# PCB.net
KiCad netlist of a schematic drawn in Altium Designer
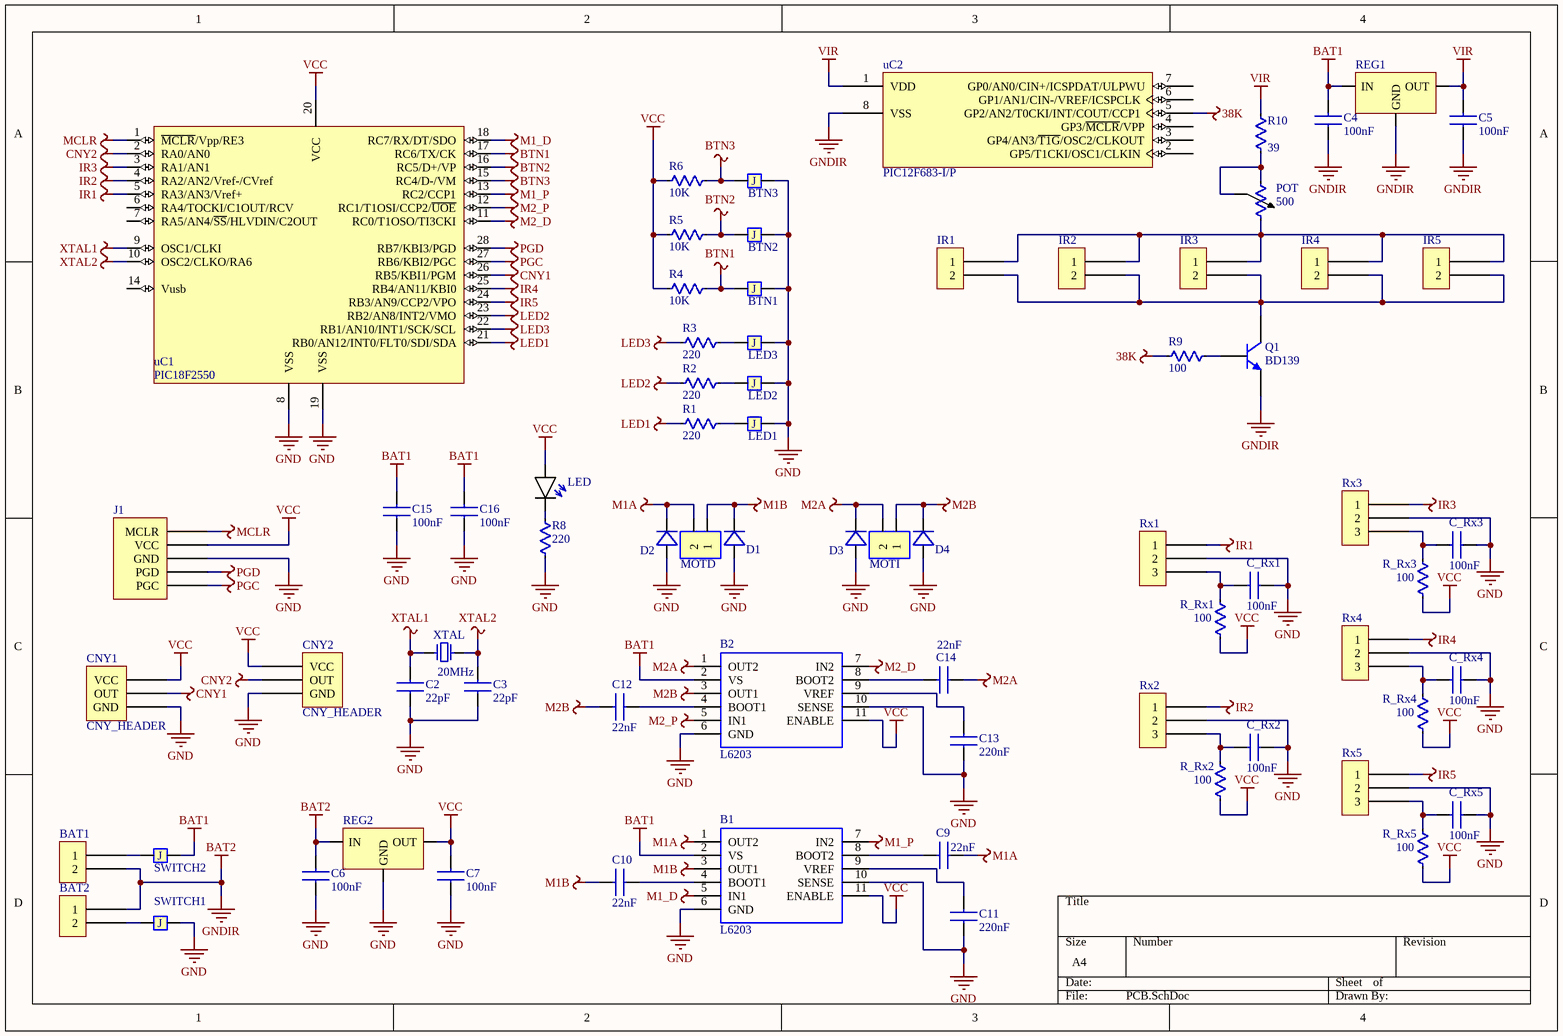
[diagram p0: PCB.SchDoc]

(export (version "E")
  (design (tool "Eeschema 10.0.6"))
  (components
    (comp (ref "B1") (value "L6203") (footprint "MUTIWATT11") (libsource (lib "L6203") (part "L6203")))
    (comp (ref "B2") (value "L6203") (footprint "MUTIWATT11") (libsource (lib "L6203") (part "L6203")))
    (comp (ref "BAT1")
      (value "~")
      (footprint "HEADER 1x2")
      (libsource (lib "AltiumLibrary") (part "Header 1x2"))
    )
    (comp (ref "BAT2")
      (value "~")
      (footprint "HEADER 1x2")
      (libsource (lib "AltiumLibrary") (part "Header 1x2"))
    )
    (comp (ref "BTN1")
      (value "JUMPER")
      (footprint "JUMPER")
      (libsource (lib "AltiumLibrary") (part "JUMPER"))
    )
    (comp (ref "BTN2")
      (value "JUMPER")
      (footprint "JUMPER")
      (libsource (lib "AltiumLibrary") (part "JUMPER"))
    )
    (comp (ref "BTN3") (value "JUMPER") (footprint "JUMPER") (libsource (lib "") (part "JUMPER_1")))
    (comp (ref "C2")
      (value "22pF")
      (footprint "CAP-CER")
      (fields (field (name "Comment") "CAP-CER"))
      (libsource (lib "AltiumLibrary") (part "CAP-CER"))
    )
    (comp (ref "C3")
      (value "22pF")
      (footprint "CAP-CER")
      (fields (field (name "Comment") "CAP-CER"))
      (libsource (lib "AltiumLibrary") (part "CAP-CER"))
    )
    (comp (ref "C4")
      (value "100nF")
      (footprint "CAP-CER")
      (fields (field (name "Comment") "CAP-CER"))
      (libsource (lib "") (part "CAP-CER_1"))
    )
    (comp (ref "C5")
      (value "100nF")
      (footprint "CAP-CER")
      (fields (field (name "Comment") "CAP-CER"))
      (libsource (lib "") (part "CAP-CER_1"))
    )
    (comp (ref "C6")
      (value "100nF")
      (footprint "CAP-CER")
      (fields (field (name "Comment") "CAP-CER"))
      (libsource (lib "") (part "CAP-CER_1"))
    )
    (comp (ref "C7")
      (value "100nF")
      (footprint "CAP-CER")
      (fields (field (name "Comment") "CAP-CER"))
      (libsource (lib "") (part "CAP-CER_1"))
    )
    (comp (ref "C9")
      (value "22nF")
      (footprint "CAP-CER")
      (fields (field (name "Comment") "CAP-CER"))
      (libsource (lib "") (part "CAP-CER_1"))
    )
    (comp (ref "C10")
      (value "22nF")
      (footprint "CAP-CER")
      (fields (field (name "Comment") "CAP-CER"))
      (libsource (lib "") (part "CAP-CER_1"))
    )
    (comp (ref "C11")
      (value "220nF")
      (footprint "CAP-CER")
      (fields (field (name "Comment") "CAP-CER"))
      (libsource (lib "") (part "CAP-CER_1"))
    )
    (comp (ref "C12")
      (value "22nF")
      (footprint "CAP-CER")
      (fields (field (name "Comment") "CAP-CER"))
      (libsource (lib "") (part "CAP-CER_1"))
    )
    (comp (ref "C13")
      (value "220nF")
      (footprint "CAP-CER")
      (fields (field (name "Comment") "CAP-CER"))
      (libsource (lib "") (part "CAP-CER_1"))
    )
    (comp (ref "C14")
      (value "22nF")
      (footprint "CAP-CER")
      (fields (field (name "Comment") "CAP-CER"))
      (libsource (lib "") (part "CAP-CER_1"))
    )
    (comp (ref "C15")
      (value "100nF")
      (footprint "CAP-CER")
      (fields (field (name "Comment") "CAP-CER"))
      (libsource (lib "") (part "CAP-CER_1"))
    )
    (comp (ref "C16")
      (value "100nF")
      (footprint "CAP-CER")
      (fields (field (name "Comment") "CAP-CER"))
      (libsource (lib "") (part "CAP-CER_1"))
    )
    (comp (ref "CNY1")
      (value "CNY_HEADER")
      (footprint "CNY_HEADER")
      (libsource (lib "") (part "CNY_HEADER_1"))
    )
    (comp (ref "CNY2")
      (value "CNY_HEADER")
      (footprint "CNY_HEADER")
      (libsource (lib "AltiumLibrary") (part "CNY_HEADER"))
    )
    (comp (ref "C_Rx1")
      (value "100nF")
      (footprint "CAP-CER")
      (fields (field (name "Comment") "CAP-CER"))
      (libsource (lib "AltiumLibrary") (part "CAP-CER"))
    )
    (comp (ref "C_Rx2")
      (value "100nF")
      (footprint "CAP-CER")
      (fields (field (name "Comment") "CAP-CER"))
      (libsource (lib "AltiumLibrary") (part "CAP-CER"))
    )
    (comp (ref "C_Rx3")
      (value "100nF")
      (footprint "CAP-CER")
      (fields (field (name "Comment") "CAP-CER"))
      (libsource (lib "AltiumLibrary") (part "CAP-CER"))
    )
    (comp (ref "C_Rx4")
      (value "100nF")
      (footprint "CAP-CER")
      (fields (field (name "Comment") "CAP-CER"))
      (libsource (lib "AltiumLibrary") (part "CAP-CER"))
    )
    (comp (ref "C_Rx5")
      (value "100nF")
      (footprint "CAP-CER")
      (fields (field (name "Comment") "CAP-CER"))
      (libsource (lib "AltiumLibrary") (part "CAP-CER"))
    )
    (comp (ref "D1") (value "DIODE") (footprint "DO-41") (libsource (lib "AltiumLibrary") (part "DIODE")))
    (comp (ref "D2") (value "DIODE") (footprint "DO-41") (libsource (lib "AltiumLibrary") (part "DIODE")))
    (comp (ref "D3") (value "DIODE") (footprint "DO-41") (libsource (lib "AltiumLibrary") (part "DIODE")))
    (comp (ref "D4") (value "DIODE") (footprint "DO-41") (libsource (lib "AltiumLibrary") (part "DIODE")))
    (comp (ref "IR1")
      (value "~")
      (footprint "HEADER 1x2")
      (libsource (lib "AltiumLibrary") (part "Header 1x2"))
    )
    (comp (ref "IR2")
      (value "~")
      (footprint "HEADER 1x2")
      (libsource (lib "AltiumLibrary") (part "Header 1x2"))
    )
    (comp (ref "IR3")
      (value "~")
      (footprint "HEADER 1x2")
      (libsource (lib "AltiumLibrary") (part "Header 1x2"))
    )
    (comp (ref "IR4")
      (value "~")
      (footprint "HEADER 1x2")
      (libsource (lib "AltiumLibrary") (part "Header 1x2"))
    )
    (comp (ref "IR5")
      (value "~")
      (footprint "HEADER 1x2")
      (libsource (lib "AltiumLibrary") (part "Header 1x2"))
    )
    (comp (ref "J1")
      (value "~")
      (footprint "Header 1x5")
      (libsource (lib "AltiumLibrary") (part "Header Programmer"))
    )
    (comp (ref "LED") (value "LED") (footprint "LED-3MM-RED") (libsource (lib "AltiumLibrary") (part "LED")))
    (comp (ref "LED1")
      (value "JUMPER")
      (footprint "JUMPER")
      (libsource (lib "AltiumLibrary") (part "JUMPER"))
    )
    (comp (ref "LED2")
      (value "JUMPER")
      (footprint "JUMPER")
      (libsource (lib "AltiumLibrary") (part "JUMPER"))
    )
    (comp (ref "LED3")
      (value "JUMPER")
      (footprint "JUMPER")
      (libsource (lib "AltiumLibrary") (part "JUMPER"))
    )
    (comp (ref "MOTD")
      (value "2-BLOCK_TERMINAL")
      (footprint "BLOCK_TERMINAL-2")
      (libsource (lib "AltiumLibrary") (part "2-BLOCK_TERMINAL"))
    )
    (comp (ref "MOTI")
      (value "2-BLOCK_TERMINAL")
      (footprint "BLOCK_TERMINAL-2")
      (libsource (lib "AltiumLibrary") (part "2-BLOCK_TERMINAL"))
    )
    (comp (ref "POT")
      (value "500")
      (footprint "POT-10TURN")
      (fields (field (name "Comment") "POT"))
      (libsource (lib "AltiumLibrary") (part "POT"))
    )
    (comp (ref "Q1") (value "BD139") (footprint "TO-126") (libsource (lib "AltiumLibrary") (part "NPN")))
    (comp (ref "R1")
      (value "220")
      (footprint "RES-Axial-400mil")
      (fields (field (name "Comment") "RES"))
      (libsource (lib "AltiumLibrary") (part "RES"))
    )
    (comp (ref "R2")
      (value "220")
      (footprint "RES-Axial-400mil")
      (fields (field (name "Comment") "RES"))
      (libsource (lib "AltiumLibrary") (part "RES"))
    )
    (comp (ref "R3")
      (value "220")
      (footprint "RES-Axial-400mil")
      (fields (field (name "Comment") "RES"))
      (libsource (lib "AltiumLibrary") (part "RES"))
    )
    (comp (ref "R4")
      (value "10K")
      (footprint "RES-Axial-400mil")
      (fields (field (name "Comment") "RES"))
      (libsource (lib "AltiumLibrary") (part "RES"))
    )
    (comp (ref "R5")
      (value "10K")
      (footprint "RES-Axial-400mil")
      (fields (field (name "Comment") "RES"))
      (libsource (lib "AltiumLibrary") (part "RES"))
    )
    (comp (ref "R6")
      (value "10K")
      (footprint "RES-Axial-400mil")
      (fields (field (name "Comment") "RES"))
      (libsource (lib "") (part "RES_1"))
    )
    (comp (ref "R8")
      (value "220")
      (footprint "RES-Axial-400mil")
      (fields (field (name "Comment") "RES"))
      (libsource (lib "") (part "RES_3"))
    )
    (comp (ref "R9")
      (value "100")
      (footprint "RES-Axial-400mil")
      (fields (field (name "Comment") "RES"))
      (libsource (lib "") (part "RES_1"))
    )
    (comp (ref "R10") (value "39") (footprint "RES-Axial-400mil") (libsource (lib "") (part "RES_3")))
    (comp (ref "REG1")
      (value "LM7805")
      (footprint "TO-220-FLAT")
      (libsource (lib "AltiumLibrary") (part "LM78XX"))
    )
    (comp (ref "REG2")
      (value "LM7805")
      (footprint "TO-220-FLAT")
      (libsource (lib "AltiumLibrary") (part "LM78XX"))
    )
    (comp (ref "Rx1")
      (value "Header 1x3")
      (footprint "Header 1x3")
      (libsource (lib "AltiumLibrary") (part "Header 1x3"))
    )
    (comp (ref "Rx2")
      (value "Header 1x3")
      (footprint "Header 1x3")
      (libsource (lib "AltiumLibrary") (part "Header 1x3"))
    )
    (comp (ref "Rx3")
      (value "Header 1x3")
      (footprint "Header 1x3")
      (libsource (lib "AltiumLibrary") (part "Header 1x3"))
    )
    (comp (ref "Rx4")
      (value "Header 1x3")
      (footprint "Header 1x3")
      (libsource (lib "AltiumLibrary") (part "Header 1x3"))
    )
    (comp (ref "Rx5")
      (value "Header 1x3")
      (footprint "Header 1x3")
      (libsource (lib "AltiumLibrary") (part "Header 1x3"))
    )
    (comp (ref "R_Rx1")
      (value "100")
      (footprint "RES-Axial-400mil")
      (fields (field (name "Comment") "RES"))
      (libsource (lib "") (part "RES_2"))
    )
    (comp (ref "R_Rx2")
      (value "100")
      (footprint "RES-Axial-400mil")
      (fields (field (name "Comment") "RES"))
      (libsource (lib "") (part "RES_2"))
    )
    (comp (ref "R_Rx3")
      (value "100")
      (footprint "RES-Axial-400mil")
      (fields (field (name "Comment") "RES"))
      (libsource (lib "") (part "RES_2"))
    )
    (comp (ref "R_Rx4")
      (value "100")
      (footprint "RES-Axial-400mil")
      (fields (field (name "Comment") "RES"))
      (libsource (lib "") (part "RES_2"))
    )
    (comp (ref "R_Rx5")
      (value "100")
      (footprint "RES-Axial-400mil")
      (fields (field (name "Comment") "RES"))
      (libsource (lib "") (part "RES_2"))
    )
    (comp (ref "SWITCH1") (value "JUMPER") (footprint "JUMPER") (libsource (lib "") (part "JUMPER_1")))
    (comp (ref "SWITCH2") (value "JUMPER") (footprint "JUMPER") (libsource (lib "") (part "JUMPER_1")))
    (comp (ref "uC1")
      (value "PIC18F2550")
      (footprint "DIP28")
      (libsource (lib "AltiumLibrary") (part "PIC18F2550"))
    )
    (comp (ref "uC2")
      (value "PIC12F683-I/P")
      (footprint "PDIP300-P8")
      (fields (field (name "PUBLISHER") "Altium Limited"))
      (libsource (lib "Microchip Microcontroller 8-Bit PIC12") (part "PIC12F683-I/P"))
    )
    (comp (ref "XTAL")
      (value "~")
      (footprint "CRYSTAL-TH")
      (fields (field (name "FREQUENCY") "20MHz"))
      (libsource (lib "AltiumLibrary") (part "XTAL"))
    )
  )
  (nets
    (net (code "1") (name "38K") (class "Default")
      (node (ref "R9") (pin "1") (pintype "passive"))
      (node (ref "uC2") (pin "5") (pinfunction "GP2/AN2/T0CKI/INT/COUT/CCP1_5") (pintype "bidirectional"))
    )
    (net (code "2") (name "BAT1") (class "Default")
      (node (ref "B1") (pin "2") (pinfunction "VS_2") (pintype "power_in"))
      (node (ref "B2") (pin "2") (pinfunction "VS_2") (pintype "power_in"))
      (node (ref "C15") (pin "2") (pintype "passive"))
      (node (ref "C16") (pin "2") (pintype "passive"))
      (node (ref "C4") (pin "2") (pintype "passive"))
      (node (ref "REG1") (pin "1") (pinfunction "IN_1") (pintype "power_in"))
      (node (ref "SWITCH2") (pin "1") (pintype "passive"))
    )
    (net (code "3") (name "BAT2") (class "Default")
      (node (ref "BAT1") (pin "2") (pinfunction "2_2") (pintype "passive"))
      (node (ref "BAT2") (pin "1") (pinfunction "1_1") (pintype "passive"))
      (node (ref "C4") (pin "1") (pintype "passive"))
      (node (ref "C5") (pin "1") (pintype "passive"))
      (node (ref "C6") (pin "2") (pintype "passive"))
      (node (ref "Q1") (pin "E") (pinfunction "E_E") (pintype "passive"))
      (node (ref "REG1") (pin "2") (pinfunction "GND_2") (pintype "power_in"))
      (node (ref "REG2") (pin "1") (pinfunction "IN_1") (pintype "power_in"))
      (node (ref "uC2") (pin "8") (pinfunction "VSS_8") (pintype "power_in"))
    )
    (net (code "4") (name "BTN1") (class "Default")
      (node (ref "BTN1") (pin "1") (pintype "passive"))
      (node (ref "R4") (pin "1") (pintype "passive"))
      (node (ref "uC1") (pin "17") (pinfunction "RC6/TX/CK_17") (pintype "bidirectional"))
    )
    (net (code "5") (name "BTN2") (class "Default")
      (node (ref "BTN2") (pin "1") (pintype "passive"))
      (node (ref "R5") (pin "1") (pintype "passive"))
      (node (ref "uC1") (pin "16") (pinfunction "RC5/D+/VP_16") (pintype "bidirectional"))
    )
    (net (code "6") (name "BTN3") (class "Default")
      (node (ref "BTN3") (pin "2") (pintype "passive"))
      (node (ref "R6") (pin "2") (pintype "passive"))
      (node (ref "uC1") (pin "15") (pinfunction "RC4/D-/VM_15") (pintype "bidirectional"))
    )
    (net (code "7") (name "CNY1") (class "Default")
      (node (ref "CNY1") (pin "3") (pinfunction "OUT_3") (pintype "passive"))
      (node (ref "uC1") (pin "26") (pinfunction "RB5/KBI1/PGM_26") (pintype "bidirectional"))
    )
    (net (code "8") (name "CNY2") (class "Default")
      (node (ref "CNY2") (pin "3") (pinfunction "OUT_3") (pintype "passive"))
      (node (ref "uC1") (pin "2") (pinfunction "RA0/AN0_2") (pintype "bidirectional"))
    )
    (net (code "9") (name "GND") (class "Default")
      (node (ref "B1") (pin "10") (pinfunction "SENSE_10") (pintype "passive"))
      (node (ref "B1") (pin "6") (pinfunction "GND_6") (pintype "passive"))
      (node (ref "B2") (pin "10") (pinfunction "SENSE_10") (pintype "passive"))
      (node (ref "B2") (pin "6") (pinfunction "GND_6") (pintype "passive"))
      (node (ref "BTN1") (pin "2") (pintype "passive"))
      (node (ref "BTN2") (pin "2") (pintype "passive"))
      (node (ref "BTN3") (pin "1") (pintype "passive"))
      (node (ref "C11") (pin "1") (pintype "passive"))
      (node (ref "C13") (pin "1") (pintype "passive"))
      (node (ref "C15") (pin "1") (pintype "passive"))
      (node (ref "C16") (pin "1") (pintype "passive"))
      (node (ref "C2") (pin "1") (pintype "passive"))
      (node (ref "C3") (pin "1") (pintype "passive"))
      (node (ref "C6") (pin "1") (pintype "passive"))
      (node (ref "C7") (pin "1") (pintype "passive"))
      (node (ref "CNY1") (pin "1") (pinfunction "GND_1") (pintype "passive"))
      (node (ref "CNY2") (pin "1") (pinfunction "GND_1") (pintype "passive"))
      (node (ref "C_Rx1") (pin "2") (pintype "passive"))
      (node (ref "C_Rx2") (pin "2") (pintype "passive"))
      (node (ref "C_Rx3") (pin "2") (pintype "passive"))
      (node (ref "C_Rx4") (pin "2") (pintype "passive"))
      (node (ref "C_Rx5") (pin "2") (pintype "passive"))
      (node (ref "D1") (pin "A") (pintype "passive"))
      (node (ref "D2") (pin "A") (pintype "passive"))
      (node (ref "D3") (pin "A") (pintype "passive"))
      (node (ref "D4") (pin "A") (pintype "passive"))
      (node (ref "J1") (pin "3") (pinfunction "GND_3") (pintype "power_in"))
      (node (ref "LED1") (pin "2") (pintype "passive"))
      (node (ref "LED2") (pin "2") (pintype "passive"))
      (node (ref "LED3") (pin "2") (pintype "passive"))
      (node (ref "R8") (pin "1") (pintype "passive"))
      (node (ref "REG2") (pin "2") (pinfunction "GND_2") (pintype "power_in"))
      (node (ref "Rx1") (pin "2") (pinfunction "2_2") (pintype "passive"))
      (node (ref "Rx2") (pin "2") (pinfunction "2_2") (pintype "passive"))
      (node (ref "Rx3") (pin "2") (pinfunction "2_2") (pintype "passive"))
      (node (ref "Rx4") (pin "2") (pinfunction "2_2") (pintype "passive"))
      (node (ref "Rx5") (pin "2") (pinfunction "2_2") (pintype "passive"))
      (node (ref "SWITCH1") (pin "1") (pintype "passive"))
      (node (ref "uC1") (pin "19") (pinfunction "VSS_19") (pintype "power_in"))
      (node (ref "uC1") (pin "8") (pinfunction "VSS_8") (pintype "power_in"))
    )
    (net (code "10") (name "IR1") (class "Default")
      (node (ref "Rx1") (pin "1") (pinfunction "1_1") (pintype "passive"))
      (node (ref "uC1") (pin "5") (pinfunction "RA3/AN3/Vref+_5") (pintype "bidirectional"))
    )
    (net (code "11") (name "IR2") (class "Default")
      (node (ref "Rx2") (pin "1") (pinfunction "1_1") (pintype "passive"))
      (node (ref "uC1") (pin "4") (pinfunction "RA2/AN2/Vref-/CVref_4") (pintype "bidirectional"))
    )
    (net (code "12") (name "IR3") (class "Default")
      (node (ref "Rx3") (pin "1") (pinfunction "1_1") (pintype "passive"))
      (node (ref "uC1") (pin "3") (pinfunction "RA1/AN1_3") (pintype "bidirectional"))
    )
    (net (code "13") (name "IR4") (class "Default")
      (node (ref "Rx4") (pin "1") (pinfunction "1_1") (pintype "passive"))
      (node (ref "uC1") (pin "25") (pinfunction "RB4/AN11/KBI0_25") (pintype "bidirectional"))
    )
    (net (code "14") (name "IR5") (class "Default")
      (node (ref "Rx5") (pin "1") (pinfunction "1_1") (pintype "passive"))
      (node (ref "uC1") (pin "24") (pinfunction "RB3/AN9/CCP2/VPO_24") (pintype "bidirectional"))
    )
    (net (code "15") (name "LED1") (class "Default")
      (node (ref "R1") (pin "2") (pintype "passive"))
      (node (ref "uC1") (pin "21") (pinfunction "RB0/AN12/INT0/FLT0/SDI/SDA_21") (pintype "bidirectional"))
    )
    (net (code "16") (name "LED2") (class "Default")
      (node (ref "R2") (pin "2") (pintype "passive"))
      (node (ref "uC1") (pin "23") (pinfunction "RB2/AN8/INT2/VMO_23") (pintype "bidirectional"))
    )
    (net (code "17") (name "LED3") (class "Default")
      (node (ref "R3") (pin "2") (pintype "passive"))
      (node (ref "uC1") (pin "22") (pinfunction "RB1/AN10/INT1/SCK/SCL_22") (pintype "bidirectional"))
    )
    (net (code "18") (name "M1A") (class "Default")
      (node (ref "B1") (pin "1") (pinfunction "OUT2_1") (pintype "passive"))
      (node (ref "C9") (pin "2") (pintype "passive"))
      (node (ref "D2") (pin "K") (pintype "passive"))
      (node (ref "MOTD") (pin "2") (pinfunction "2_2") (pintype "passive"))
    )
    (net (code "19") (name "M1B") (class "Default")
      (node (ref "B1") (pin "3") (pinfunction "OUT1_3") (pintype "passive"))
      (node (ref "C10") (pin "1") (pintype "passive"))
      (node (ref "D1") (pin "K") (pintype "passive"))
      (node (ref "MOTD") (pin "1") (pinfunction "1_1") (pintype "passive"))
    )
    (net (code "20") (name "M1_D") (class "Default")
      (node (ref "B1") (pin "5") (pinfunction "IN1_5") (pintype "passive"))
      (node (ref "uC1") (pin "18") (pinfunction "RC7/RX/DT/SDO_18") (pintype "bidirectional"))
    )
    (net (code "21") (name "M1_P") (class "Default")
      (node (ref "B1") (pin "7") (pinfunction "IN2_7") (pintype "passive"))
      (node (ref "uC1") (pin "13") (pinfunction "RC2/CCP1_13") (pintype "bidirectional"))
    )
    (net (code "22") (name "M2A") (class "Default")
      (node (ref "B2") (pin "1") (pinfunction "OUT2_1") (pintype "passive"))
      (node (ref "C14") (pin "2") (pintype "passive"))
      (node (ref "D3") (pin "K") (pintype "passive"))
      (node (ref "MOTI") (pin "2") (pinfunction "2_2") (pintype "passive"))
    )
    (net (code "23") (name "M2B") (class "Default")
      (node (ref "B2") (pin "3") (pinfunction "OUT1_3") (pintype "passive"))
      (node (ref "C12") (pin "1") (pintype "passive"))
      (node (ref "D4") (pin "K") (pintype "passive"))
      (node (ref "MOTI") (pin "1") (pinfunction "1_1") (pintype "passive"))
    )
    (net (code "24") (name "M2_D") (class "Default")
      (node (ref "B2") (pin "7") (pinfunction "IN2_7") (pintype "passive"))
      (node (ref "uC1") (pin "11") (pinfunction "RC0/T1OSO/TI3CKI_11") (pintype "bidirectional"))
    )
    (net (code "25") (name "M2_P") (class "Default")
      (node (ref "B2") (pin "5") (pinfunction "IN1_5") (pintype "passive"))
      (node (ref "uC1") (pin "12") (pinfunction "RC1/T1OSI/CCP2/~{UOE}_12") (pintype "bidirectional"))
    )
    (net (code "26") (name "MCLR") (class "Default")
      (node (ref "J1") (pin "1") (pinfunction "MCLR_1") (pintype "passive"))
      (node (ref "uC1") (pin "1") (pinfunction "~{MCLR}/Vpp/RE3_1") (pintype "bidirectional"))
    )
    (net (code "27") (name "Net-(B1-BOOT1)") (class "Default")
      (node (ref "B1") (pin "4") (pinfunction "BOOT1_4") (pintype "passive"))
      (node (ref "C10") (pin "2") (pintype "passive"))
    )
    (net (code "28") (name "Net-(B1-BOOT2)") (class "Default")
      (node (ref "B1") (pin "8") (pinfunction "BOOT2_8") (pintype "passive"))
      (node (ref "C9") (pin "1") (pintype "passive"))
    )
    (net (code "29") (name "Net-(B1-VREF)") (class "Default")
      (node (ref "B1") (pin "9") (pinfunction "VREF_9") (pintype "power_in"))
      (node (ref "C11") (pin "2") (pintype "passive"))
    )
    (net (code "30") (name "Net-(B2-BOOT1)") (class "Default")
      (node (ref "B2") (pin "4") (pinfunction "BOOT1_4") (pintype "passive"))
      (node (ref "C12") (pin "2") (pintype "passive"))
    )
    (net (code "31") (name "Net-(B2-BOOT2)") (class "Default")
      (node (ref "B2") (pin "8") (pinfunction "BOOT2_8") (pintype "passive"))
      (node (ref "C14") (pin "1") (pintype "passive"))
    )
    (net (code "32") (name "Net-(B2-VREF)") (class "Default")
      (node (ref "B2") (pin "9") (pinfunction "VREF_9") (pintype "power_in"))
      (node (ref "C13") (pin "2") (pintype "passive"))
    )
    (net (code "33") (name "Net-(BAT1-Pad1)") (class "Default")
      (node (ref "BAT1") (pin "1") (pinfunction "1_1") (pintype "passive"))
      (node (ref "SWITCH2") (pin "2") (pintype "passive"))
    )
    (net (code "34") (name "Net-(BAT2-Pad2)") (class "Default")
      (node (ref "BAT2") (pin "2") (pinfunction "2_2") (pintype "passive"))
      (node (ref "SWITCH1") (pin "2") (pintype "passive"))
    )
    (net (code "35") (name "Net-(C_Rx1-Pad1)") (class "Default")
      (node (ref "C_Rx1") (pin "1") (pintype "passive"))
      (node (ref "R_Rx1") (pin "2") (pintype "passive"))
      (node (ref "Rx1") (pin "3") (pinfunction "3_3") (pintype "passive"))
    )
    (net (code "36") (name "Net-(C_Rx2-Pad1)") (class "Default")
      (node (ref "C_Rx2") (pin "1") (pintype "passive"))
      (node (ref "R_Rx2") (pin "2") (pintype "passive"))
      (node (ref "Rx2") (pin "3") (pinfunction "3_3") (pintype "passive"))
    )
    (net (code "37") (name "Net-(C_Rx3-Pad1)") (class "Default")
      (node (ref "C_Rx3") (pin "1") (pintype "passive"))
      (node (ref "R_Rx3") (pin "2") (pintype "passive"))
      (node (ref "Rx3") (pin "3") (pinfunction "3_3") (pintype "passive"))
    )
    (net (code "38") (name "Net-(C_Rx4-Pad1)") (class "Default")
      (node (ref "C_Rx4") (pin "1") (pintype "passive"))
      (node (ref "R_Rx4") (pin "2") (pintype "passive"))
      (node (ref "Rx4") (pin "3") (pinfunction "3_3") (pintype "passive"))
    )
    (net (code "39") (name "Net-(C_Rx5-Pad1)") (class "Default")
      (node (ref "C_Rx5") (pin "1") (pintype "passive"))
      (node (ref "R_Rx5") (pin "2") (pintype "passive"))
      (node (ref "Rx5") (pin "3") (pinfunction "3_3") (pintype "passive"))
    )
    (net (code "40") (name "Net-(IR1-Pad1)") (class "Default")
      (node (ref "IR1") (pin "1") (pinfunction "1_1") (pintype "passive"))
      (node (ref "IR2") (pin "1") (pinfunction "1_1") (pintype "passive"))
      (node (ref "IR3") (pin "1") (pinfunction "1_1") (pintype "passive"))
      (node (ref "IR4") (pin "1") (pinfunction "1_1") (pintype "passive"))
      (node (ref "IR5") (pin "1") (pinfunction "1_1") (pintype "passive"))
      (node (ref "POT") (pin "1") (pintype "passive"))
    )
    (net (code "41") (name "Net-(IR1-Pad2)") (class "Default")
      (node (ref "IR1") (pin "2") (pinfunction "2_2") (pintype "passive"))
      (node (ref "IR2") (pin "2") (pinfunction "2_2") (pintype "passive"))
      (node (ref "IR3") (pin "2") (pinfunction "2_2") (pintype "passive"))
      (node (ref "IR4") (pin "2") (pinfunction "2_2") (pintype "passive"))
      (node (ref "IR5") (pin "2") (pinfunction "2_2") (pintype "passive"))
      (node (ref "Q1") (pin "C") (pinfunction "C_C") (pintype "passive"))
    )
    (net (code "42") (name "Net-(LED-PadK)") (class "Default")
      (node (ref "LED") (pin "K") (pintype "passive"))
      (node (ref "R8") (pin "2") (pintype "passive"))
    )
    (net (code "43") (name "Net-(LED1-Pad1)") (class "Default")
      (node (ref "LED1") (pin "1") (pintype "passive"))
      (node (ref "R1") (pin "1") (pintype "passive"))
    )
    (net (code "44") (name "Net-(LED2-Pad1)") (class "Default")
      (node (ref "LED2") (pin "1") (pintype "passive"))
      (node (ref "R2") (pin "1") (pintype "passive"))
    )
    (net (code "45") (name "Net-(LED3-Pad1)") (class "Default")
      (node (ref "LED3") (pin "1") (pintype "passive"))
      (node (ref "R3") (pin "1") (pintype "passive"))
    )
    (net (code "46") (name "Net-(POT-Pad2)") (class "Default")
      (node (ref "POT") (pin "2") (pintype "passive"))
      (node (ref "POT") (pin "3") (pintype "passive"))
      (node (ref "R10") (pin "1") (pintype "passive"))
    )
    (net (code "47") (name "Net-(Q1-PadB)") (class "Default")
      (node (ref "Q1") (pin "B") (pinfunction "B_B") (pintype "passive"))
      (node (ref "R9") (pin "2") (pintype "passive"))
    )
    (net (code "48") (name "PGC") (class "Default")
      (node (ref "J1") (pin "5") (pinfunction "PGC_5") (pintype "passive"))
      (node (ref "uC1") (pin "27") (pinfunction "RB6/KBI2/PGC_27") (pintype "bidirectional"))
    )
    (net (code "49") (name "PGD") (class "Default")
      (node (ref "J1") (pin "4") (pinfunction "PGD_4") (pintype "passive"))
      (node (ref "uC1") (pin "28") (pinfunction "RB7/KBI3/PGD_28") (pintype "bidirectional"))
    )
    (net (code "50") (name "VCC") (class "Default")
      (node (ref "B1") (pin "11") (pinfunction "ENABLE_11") (pintype "passive"))
      (node (ref "B2") (pin "11") (pinfunction "ENABLE_11") (pintype "passive"))
      (node (ref "C7") (pin "2") (pintype "passive"))
      (node (ref "CNY1") (pin "2") (pinfunction "VCC_2") (pintype "passive"))
      (node (ref "CNY2") (pin "2") (pinfunction "VCC_2") (pintype "passive"))
      (node (ref "J1") (pin "2") (pinfunction "VCC_2") (pintype "power_in"))
      (node (ref "LED") (pin "A") (pintype "passive"))
      (node (ref "R4") (pin "2") (pintype "passive"))
      (node (ref "R5") (pin "2") (pintype "passive"))
      (node (ref "R6") (pin "1") (pintype "passive"))
      (node (ref "REG2") (pin "3") (pinfunction "OUT_3") (pintype "power_in"))
      (node (ref "R_Rx1") (pin "1") (pintype "passive"))
      (node (ref "R_Rx2") (pin "1") (pintype "passive"))
      (node (ref "R_Rx3") (pin "1") (pintype "passive"))
      (node (ref "R_Rx4") (pin "1") (pintype "passive"))
      (node (ref "R_Rx5") (pin "1") (pintype "passive"))
      (node (ref "uC1") (pin "20") (pinfunction "VCC_20") (pintype "power_in"))
    )
    (net (code "51") (name "VIR") (class "Default")
      (node (ref "C5") (pin "2") (pintype "passive"))
      (node (ref "R10") (pin "2") (pintype "passive"))
      (node (ref "REG1") (pin "3") (pinfunction "OUT_3") (pintype "power_in"))
      (node (ref "uC2") (pin "1") (pinfunction "VDD_1") (pintype "power_in"))
    )
    (net (code "52") (name "XTAL1") (class "Default")
      (node (ref "C2") (pin "2") (pintype "passive"))
      (node (ref "XTAL") (pin "1") (pintype "passive"))
      (node (ref "uC1") (pin "9") (pinfunction "OSC1/CLKI_9") (pintype "bidirectional"))
    )
    (net (code "53") (name "XTAL2") (class "Default")
      (node (ref "C3") (pin "2") (pintype "passive"))
      (node (ref "XTAL") (pin "2") (pintype "passive"))
      (node (ref "uC1") (pin "10") (pinfunction "OSC2/CLKO/RA6_10") (pintype "bidirectional"))
    )
    (net (code "54") (name "unconnected-(uC1-RA4{slash}TOCKI{slash}C1OUT{slash}RCV-Pad6)") (class "Default")
      (node (ref "uC1") (pin "6") (pinfunction "RA4/TOCKI/C1OUT/RCV_6") (pintype "bidirectional"))
    )
    (net (code "55") (name "unconnected-(uC1-RA5{slash}AN4{slash}~{SS}{slash}HLVDIN{slash}C2OUT-Pad7)") (class "Default")
      (node (ref "uC1") (pin "7") (pinfunction "RA5/AN4/~{SS}/HLVDIN/C2OUT_7") (pintype "bidirectional"))
    )
    (net (code "56") (name "unconnected-(uC1-Vusb-Pad14)") (class "Default")
      (node (ref "uC1") (pin "14") (pinfunction "Vusb_14") (pintype "bidirectional"))
    )
    (net (code "57") (name "unconnected-(uC2-GP0{slash}AN0{slash}CIN+{slash}ICSPDAT{slash}ULPWU-Pad7)") (class "Default")
      (node (ref "uC2") (pin "7") (pinfunction "GP0/AN0/CIN+/ICSPDAT/ULPWU_7") (pintype "bidirectional"))
    )
    (net (code "58") (name "unconnected-(uC2-GP1{slash}AN1{slash}CIN-{slash}VREF{slash}ICSPCLK-Pad6)") (class "Default")
      (node (ref "uC2") (pin "6") (pinfunction "GP1/AN1/CIN-/VREF/ICSPCLK_6") (pintype "bidirectional"))
    )
    (net (code "59") (name "unconnected-(uC2-GP3{slash}~{MCLR}{slash}VPP-Pad4)") (class "Default")
      (node (ref "uC2") (pin "4") (pinfunction "GP3/~{MCLR}/VPP_4") (pintype "bidirectional"))
    )
    (net (code "60") (name "unconnected-(uC2-GP4{slash}AN3{slash}~{T1G}{slash}OSC2{slash}CLKOUT-Pad3)") (class "Default")
      (node (ref "uC2") (pin "3") (pinfunction "GP4/AN3/~{T1G}/OSC2/CLKOUT_3") (pintype "bidirectional"))
    )
    (net (code "61") (name "unconnected-(uC2-GP5{slash}T1CKI{slash}OSC1{slash}CLKIN-Pad2)") (class "Default")
      (node (ref "uC2") (pin "2") (pinfunction "GP5/T1CKI/OSC1/CLKIN_2") (pintype "bidirectional"))
    )
  )
)
